# E3.net
KiCad netlist of a schematic drawn in Altium Designer
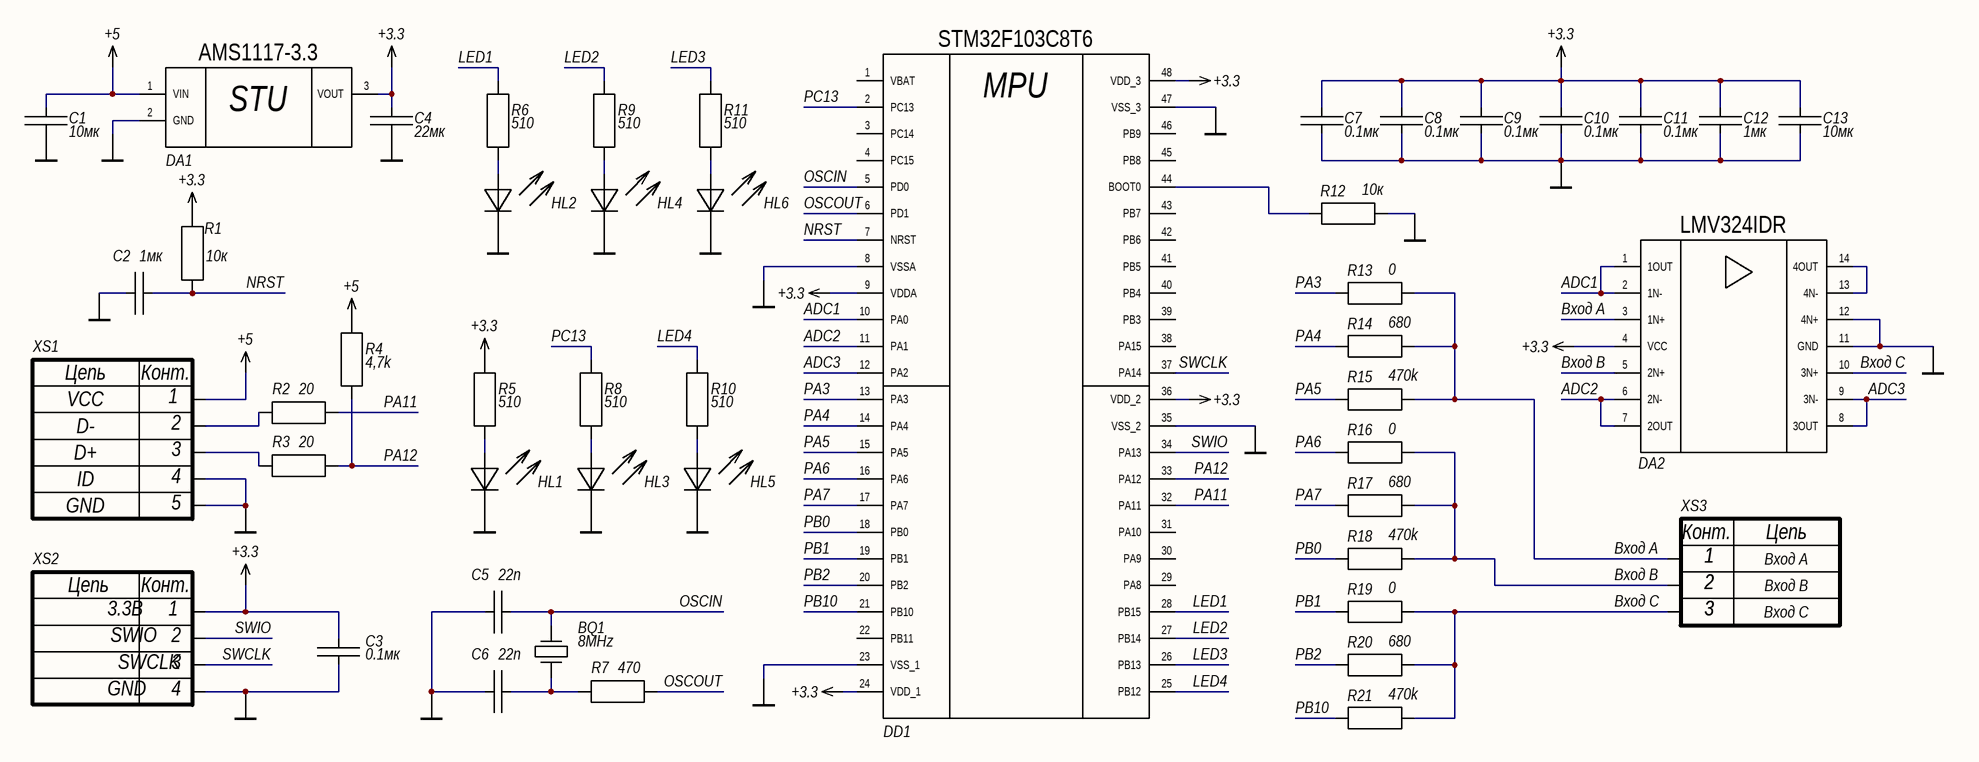
[diagram p0: E3.SchDoc]

(export (version "E")
  (design (tool "Eeschema 10.0.6"))
  (components
    (comp (ref "BQ1")
      (value "8MHz")
      (footprint "PcbLib:Crystal Resonator")
      (libsource (lib "Schlib") (part "Quartz resonator"))
    )
    (comp (ref "C1") (value "10мк") (footprint "PcbLib:C SMD 0603") (libsource (lib "Schlib") (part "C")))
    (comp (ref "C2") (value "1мк") (footprint "PcbLib:C SMD 0603") (libsource (lib "Schlib") (part "C")))
    (comp (ref "C3") (value "0.1мк") (footprint "PcbLib:C SMD 0603") (libsource (lib "Schlib") (part "C")))
    (comp (ref "C4") (value "22мк") (footprint "PcbLib:C SMD 0603") (libsource (lib "Schlib") (part "C")))
    (comp (ref "C5") (value "22п") (footprint "PcbLib:C SMD 0603") (libsource (lib "Schlib") (part "C")))
    (comp (ref "C6") (value "22п") (footprint "PcbLib:C SMD 0603") (libsource (lib "Schlib") (part "C")))
    (comp (ref "C7") (value "0.1мк") (footprint "PcbLib:C SMD 0603") (libsource (lib "Schlib") (part "C")))
    (comp (ref "C8") (value "0.1мк") (footprint "PcbLib:C SMD 0603") (libsource (lib "Schlib") (part "C")))
    (comp (ref "C9") (value "0.1мк") (footprint "PcbLib:C SMD 0603") (libsource (lib "Schlib") (part "C")))
    (comp (ref "C10") (value "0.1мк") (footprint "PcbLib:C SMD 0603") (libsource (lib "Schlib") (part "C")))
    (comp (ref "C11") (value "0.1мк") (footprint "PcbLib:C SMD 0603") (libsource (lib "Schlib") (part "C")))
    (comp (ref "C12") (value "1мк") (footprint "PcbLib:C SMD 0603") (libsource (lib "Schlib") (part "C")))
    (comp (ref "C13") (value "10мк") (footprint "PcbLib:C SMD 0603") (libsource (lib "Schlib") (part "C")))
    (comp (ref "DA1")
      (value "Stabilizer")
      (footprint "SOT230P695X180-4N")
      (libsource (lib "Schlib") (part "Stabilizer"))
    )
    (comp (ref "DA2")
      (value "OpAmp LM358DR [SOIC-14]")
      (footprint "SOP127P600X175-14N")
      (libsource (lib "Schlib") (part "OpAmp LM358DR [SOIC-14]"))
    )
    (comp (ref "DD1")
      (value "STM32F103C8T6 [LQFP-48]")
      (footprint "STM32 [LQFP-48]")
      (description "32bit MCU ARM Cortex-M3 72MHz")
      (libsource (lib "Schlib") (part "STM32F103C8T6 [LQFP-48]"))
    )
    (comp (ref "HL1") (value "LED") (footprint "PcbLib:Led 1206") (libsource (lib "MKlib") (part "LED")))
    (comp (ref "HL2") (value "LED") (footprint "PcbLib:Led 1206") (libsource (lib "MKlib") (part "LED")))
    (comp (ref "HL3") (value "LED") (footprint "PcbLib:Led 1206") (libsource (lib "MKlib") (part "LED")))
    (comp (ref "HL4") (value "LED") (footprint "PcbLib:Led 1206") (libsource (lib "MKlib") (part "LED")))
    (comp (ref "HL5") (value "LED") (footprint "PcbLib:Led 1206") (libsource (lib "MKlib") (part "LED")))
    (comp (ref "HL6") (value "LED") (footprint "PcbLib:Led 1206") (libsource (lib "MKlib") (part "LED")))
    (comp (ref "R1") (value "10к") (footprint "R_SMD_1206") (libsource (lib "Schlib") (part "R")))
    (comp (ref "R2") (value "20") (footprint "R_SMD_1206") (libsource (lib "Schlib") (part "R")))
    (comp (ref "R3") (value "20") (footprint "R_SMD_1206") (libsource (lib "Schlib") (part "R")))
    (comp (ref "R4") (value "4,7k") (footprint "R_SMD_1206") (libsource (lib "Schlib") (part "R")))
    (comp (ref "R5") (value "510") (footprint "R_SMD_1206") (libsource (lib "Schlib") (part "R")))
    (comp (ref "R6") (value "510") (footprint "R_SMD_1206") (libsource (lib "Schlib") (part "R")))
    (comp (ref "R7") (value "470") (footprint "R_SMD_1206") (libsource (lib "Schlib") (part "R")))
    (comp (ref "R8") (value "510") (footprint "R_SMD_1206") (libsource (lib "Schlib") (part "R")))
    (comp (ref "R9") (value "510") (footprint "R_SMD_1206") (libsource (lib "Schlib") (part "R")))
    (comp (ref "R10") (value "510") (footprint "R_SMD_1206") (libsource (lib "Schlib") (part "R")))
    (comp (ref "R11") (value "510") (footprint "R_SMD_1206") (libsource (lib "Schlib") (part "R")))
    (comp (ref "R12") (value "10к") (footprint "R_SMD_1206") (libsource (lib "Schlib") (part "R")))
    (comp (ref "R13") (value "0") (footprint "R_SMD_1206") (libsource (lib "Schlib") (part "R")))
    (comp (ref "R14") (value "680") (footprint "R_SMD_1206") (libsource (lib "Schlib") (part "R")))
    (comp (ref "R15") (value "470k") (footprint "R_SMD_1206") (libsource (lib "Schlib") (part "R")))
    (comp (ref "R16") (value "0") (footprint "R_SMD_1206") (libsource (lib "Schlib") (part "R")))
    (comp (ref "R17") (value "680") (footprint "R_SMD_1206") (libsource (lib "Schlib") (part "R")))
    (comp (ref "R18") (value "470k") (footprint "R_SMD_1206") (libsource (lib "Schlib") (part "R")))
    (comp (ref "R19") (value "0") (footprint "R_SMD_1206") (libsource (lib "Schlib") (part "R")))
    (comp (ref "R20") (value "680") (footprint "R_SMD_1206") (libsource (lib "Schlib") (part "R")))
    (comp (ref "R21") (value "470k") (footprint "R_SMD_1206") (libsource (lib "Schlib") (part "R")))
    (comp (ref "XS1")
      (value "USB_B")
      (footprint "USB 2.0 Type B Mini")
      (libsource (lib "Schlib") (part "USB"))
    )
    (comp (ref "XS2") (value "SWD") (footprint "PLS-4") (libsource (lib "Schlib") (part "XS_SWD")))
    (comp (ref "XS3")
      (value "XS3")
      (footprint "PcbLib:ZIF 14P socket")
      (description "ZIF 14P socket")
      (libsource (lib "Schlib") (part "XS3"))
    )
  )
  (nets
    (net (code "1") (name "+3.3") (class "Default")
      (node (ref "C10") (pin "1") (pinfunction "1_1") (pintype "passive"))
      (node (ref "C11") (pin "1") (pinfunction "1_1") (pintype "passive"))
      (node (ref "C12") (pin "1") (pinfunction "1_1") (pintype "passive"))
      (node (ref "C13") (pin "1") (pinfunction "1_1") (pintype "passive"))
      (node (ref "C3") (pin "1") (pinfunction "1_1") (pintype "passive"))
      (node (ref "C4") (pin "1") (pinfunction "1_1") (pintype "passive"))
      (node (ref "C7") (pin "1") (pinfunction "1_1") (pintype "passive"))
      (node (ref "C8") (pin "1") (pinfunction "1_1") (pintype "passive"))
      (node (ref "C9") (pin "1") (pinfunction "1_1") (pintype "passive"))
      (node (ref "DA1") (pin "3") (pinfunction "VOUT_3") (pintype "passive"))
      (node (ref "DA2") (pin "4") (pinfunction "VCC_4") (pintype "passive"))
      (node (ref "DD1") (pin "24") (pinfunction "VDD_1_24") (pintype "passive"))
      (node (ref "DD1") (pin "36") (pinfunction "VDD_2_36") (pintype "passive"))
      (node (ref "DD1") (pin "48") (pinfunction "VDD_3_48") (pintype "passive"))
      (node (ref "DD1") (pin "9") (pinfunction "VDDA_9") (pintype "passive"))
      (node (ref "R1") (pin "1") (pinfunction "1_1") (pintype "passive"))
      (node (ref "R5") (pin "1") (pinfunction "1_1") (pintype "passive"))
      (node (ref "XS2") (pin "4") (pinfunction "3.3В_4") (pintype "passive"))
    )
    (net (code "2") (name "+5") (class "Default")
      (node (ref "C1") (pin "1") (pinfunction "1_1") (pintype "passive"))
      (node (ref "DA1") (pin "1") (pinfunction "VIN_1") (pintype "passive"))
      (node (ref "R4") (pin "2") (pinfunction "2_2") (pintype "passive"))
      (node (ref "XS1") (pin "1") (pinfunction "1_1") (pintype "passive"))
    )
    (net (code "3") (name "/ADC1") (class "Default")
      (node (ref "DA2") (pin "1") (pinfunction "1OUT_1") (pintype "passive"))
      (node (ref "DA2") (pin "2") (pinfunction "1N-_2") (pintype "passive"))
      (node (ref "DD1") (pin "10") (pinfunction "PA0_10") (pintype "passive"))
    )
    (net (code "4") (name "/ADC2") (class "Default")
      (node (ref "DA2") (pin "6") (pinfunction "2N-_6") (pintype "passive"))
      (node (ref "DA2") (pin "7") (pinfunction "2OUT_7") (pintype "passive"))
      (node (ref "DD1") (pin "11") (pinfunction "PA1_11") (pintype "passive"))
    )
    (net (code "5") (name "/ADC3") (class "Default")
      (node (ref "DA2") (pin "8") (pinfunction "3OUT_8") (pintype "passive"))
      (node (ref "DA2") (pin "9") (pinfunction "3N-_9") (pintype "passive"))
      (node (ref "DD1") (pin "12") (pinfunction "PA2_12") (pintype "passive"))
    )
    (net (code "6") (name "/LED1") (class "Default")
      (node (ref "DD1") (pin "28") (pinfunction "PB15_28") (pintype "passive"))
      (node (ref "R6") (pin "1") (pinfunction "1_1") (pintype "passive"))
    )
    (net (code "7") (name "/LED2") (class "Default")
      (node (ref "DD1") (pin "27") (pinfunction "PB14_27") (pintype "passive"))
      (node (ref "R9") (pin "1") (pinfunction "1_1") (pintype "passive"))
    )
    (net (code "8") (name "/LED3") (class "Default")
      (node (ref "DD1") (pin "26") (pinfunction "PB13_26") (pintype "passive"))
      (node (ref "R11") (pin "1") (pinfunction "1_1") (pintype "passive"))
    )
    (net (code "9") (name "/LED4") (class "Default")
      (node (ref "DD1") (pin "25") (pinfunction "PB12_25") (pintype "passive"))
      (node (ref "R10") (pin "1") (pinfunction "1_1") (pintype "passive"))
    )
    (net (code "10") (name "/NRST") (class "Default")
      (node (ref "C2") (pin "1") (pinfunction "1_1") (pintype "passive"))
      (node (ref "DD1") (pin "7") (pinfunction "NRST_7") (pintype "passive"))
      (node (ref "R1") (pin "2") (pinfunction "2_2") (pintype "passive"))
    )
    (net (code "11") (name "/OSCIN") (class "Default")
      (node (ref "BQ1") (pin "1") (pinfunction "1_1") (pintype "passive"))
      (node (ref "C5") (pin "2") (pinfunction "2_2") (pintype "passive"))
      (node (ref "DD1") (pin "5") (pinfunction "PD0_5") (pintype "passive"))
    )
    (net (code "12") (name "/OSCOUT") (class "Default")
      (node (ref "DD1") (pin "6") (pinfunction "PD1_6") (pintype "passive"))
      (node (ref "R7") (pin "2") (pinfunction "2_2") (pintype "passive"))
    )
    (net (code "13") (name "/PA3") (class "Default")
      (node (ref "DD1") (pin "13") (pinfunction "PA3_13") (pintype "passive"))
      (node (ref "R13") (pin "2") (pinfunction "2_2") (pintype "passive"))
    )
    (net (code "14") (name "/PA4") (class "Default")
      (node (ref "DD1") (pin "14") (pinfunction "PA4_14") (pintype "passive"))
      (node (ref "R14") (pin "2") (pinfunction "2_2") (pintype "passive"))
    )
    (net (code "15") (name "/PA5") (class "Default")
      (node (ref "DD1") (pin "15") (pinfunction "PA5_15") (pintype "passive"))
      (node (ref "R15") (pin "2") (pinfunction "2_2") (pintype "passive"))
    )
    (net (code "16") (name "/PA6") (class "Default")
      (node (ref "DD1") (pin "16") (pinfunction "PA6_16") (pintype "passive"))
      (node (ref "R16") (pin "2") (pinfunction "2_2") (pintype "passive"))
    )
    (net (code "17") (name "/PA7") (class "Default")
      (node (ref "DD1") (pin "17") (pinfunction "PA7_17") (pintype "passive"))
      (node (ref "R17") (pin "2") (pinfunction "2_2") (pintype "passive"))
    )
    (net (code "18") (name "/PA11") (class "Default")
      (node (ref "DD1") (pin "32") (pinfunction "PA11_32") (pintype "passive"))
      (node (ref "R2") (pin "2") (pinfunction "2_2") (pintype "passive"))
    )
    (net (code "19") (name "/PA12") (class "Default")
      (node (ref "DD1") (pin "33") (pinfunction "PA12_33") (pintype "passive"))
      (node (ref "R3") (pin "2") (pinfunction "2_2") (pintype "passive"))
      (node (ref "R4") (pin "1") (pinfunction "1_1") (pintype "passive"))
    )
    (net (code "20") (name "/PB0") (class "Default")
      (node (ref "DD1") (pin "18") (pinfunction "PB0_18") (pintype "passive"))
      (node (ref "R18") (pin "2") (pinfunction "2_2") (pintype "passive"))
    )
    (net (code "21") (name "/PB1") (class "Default")
      (node (ref "DD1") (pin "19") (pinfunction "PB1_19") (pintype "passive"))
      (node (ref "R19") (pin "2") (pinfunction "2_2") (pintype "passive"))
    )
    (net (code "22") (name "/PB2") (class "Default")
      (node (ref "DD1") (pin "20") (pinfunction "PB2_20") (pintype "passive"))
      (node (ref "R20") (pin "2") (pinfunction "2_2") (pintype "passive"))
    )
    (net (code "23") (name "/PB10") (class "Default")
      (node (ref "DD1") (pin "21") (pinfunction "PB10_21") (pintype "passive"))
      (node (ref "R21") (pin "2") (pinfunction "2_2") (pintype "passive"))
    )
    (net (code "24") (name "/PC13") (class "Default")
      (node (ref "DD1") (pin "2") (pinfunction "PC13_2") (pintype "passive"))
      (node (ref "R8") (pin "1") (pinfunction "1_1") (pintype "passive"))
    )
    (net (code "25") (name "/SWCLK") (class "Default")
      (node (ref "DD1") (pin "37") (pinfunction "PA14_37") (pintype "passive"))
      (node (ref "XS2") (pin "2") (pinfunction "SWCLK_2") (pintype "passive"))
    )
    (net (code "26") (name "/SWIO") (class "Default")
      (node (ref "DD1") (pin "34") (pinfunction "PA13_34") (pintype "passive"))
      (node (ref "XS2") (pin "3") (pinfunction "SWIO_3") (pintype "passive"))
    )
    (net (code "27") (name "/Вход A") (class "Default")
      (node (ref "DA2") (pin "3") (pinfunction "1N+_3") (pintype "passive"))
      (node (ref "R13") (pin "1") (pinfunction "1_1") (pintype "passive"))
      (node (ref "R14") (pin "1") (pinfunction "1_1") (pintype "passive"))
      (node (ref "R15") (pin "1") (pinfunction "1_1") (pintype "passive"))
      (node (ref "XS3") (pin "1") (pinfunction "1_1") (pintype "passive"))
    )
    (net (code "28") (name "/Вход B") (class "Default")
      (node (ref "DA2") (pin "5") (pinfunction "2N+_5") (pintype "passive"))
      (node (ref "R16") (pin "1") (pinfunction "1_1") (pintype "passive"))
      (node (ref "R17") (pin "1") (pinfunction "1_1") (pintype "passive"))
      (node (ref "R18") (pin "1") (pinfunction "1_1") (pintype "passive"))
      (node (ref "XS3") (pin "2") (pinfunction "2_2") (pintype "passive"))
    )
    (net (code "29") (name "/Вход C") (class "Default")
      (node (ref "DA2") (pin "10") (pinfunction "3N+_10") (pintype "passive"))
      (node (ref "R19") (pin "1") (pinfunction "1_1") (pintype "passive"))
      (node (ref "R20") (pin "1") (pinfunction "1_1") (pintype "passive"))
      (node (ref "R21") (pin "1") (pinfunction "1_1") (pintype "passive"))
      (node (ref "XS3") (pin "3") (pinfunction "3_3") (pintype "passive"))
    )
    (net (code "30") (name "GND") (class "Default")
      (node (ref "C1") (pin "2") (pinfunction "2_2") (pintype "passive"))
      (node (ref "C10") (pin "2") (pinfunction "2_2") (pintype "passive"))
      (node (ref "C11") (pin "2") (pinfunction "2_2") (pintype "passive"))
      (node (ref "C12") (pin "2") (pinfunction "2_2") (pintype "passive"))
      (node (ref "C13") (pin "2") (pinfunction "2_2") (pintype "passive"))
      (node (ref "C2") (pin "2") (pinfunction "2_2") (pintype "passive"))
      (node (ref "C3") (pin "2") (pinfunction "2_2") (pintype "passive"))
      (node (ref "C4") (pin "2") (pinfunction "2_2") (pintype "passive"))
      (node (ref "C5") (pin "1") (pinfunction "1_1") (pintype "passive"))
      (node (ref "C6") (pin "1") (pinfunction "1_1") (pintype "passive"))
      (node (ref "C7") (pin "2") (pinfunction "2_2") (pintype "passive"))
      (node (ref "C8") (pin "2") (pinfunction "2_2") (pintype "passive"))
      (node (ref "C9") (pin "2") (pinfunction "2_2") (pintype "passive"))
      (node (ref "DA1") (pin "2") (pinfunction "GND_2") (pintype "passive"))
      (node (ref "DA2") (pin "11") (pinfunction "GND_11") (pintype "passive"))
      (node (ref "DA2") (pin "12") (pinfunction "4N+_12") (pintype "passive"))
      (node (ref "DD1") (pin "23") (pinfunction "VSS_1_23") (pintype "passive"))
      (node (ref "DD1") (pin "35") (pinfunction "VSS_2_35") (pintype "passive"))
      (node (ref "DD1") (pin "47") (pinfunction "VSS_3_47") (pintype "passive"))
      (node (ref "DD1") (pin "8") (pinfunction "VSSA_8") (pintype "passive"))
      (node (ref "HL1") (pin "1") (pinfunction "1_1") (pintype "passive"))
      (node (ref "HL2") (pin "1") (pinfunction "1_1") (pintype "passive"))
      (node (ref "HL3") (pin "1") (pinfunction "1_1") (pintype "passive"))
      (node (ref "HL4") (pin "1") (pinfunction "1_1") (pintype "passive"))
      (node (ref "HL5") (pin "1") (pinfunction "1_1") (pintype "passive"))
      (node (ref "HL6") (pin "1") (pinfunction "1_1") (pintype "passive"))
      (node (ref "R12") (pin "1") (pinfunction "1_1") (pintype "passive"))
      (node (ref "XS1") (pin "4") (pinfunction "4_4") (pintype "passive"))
      (node (ref "XS1") (pin "5") (pinfunction "5_5") (pintype "passive"))
      (node (ref "XS2") (pin "1") (pinfunction "GND_1") (pintype "passive"))
    )
    (net (code "31") (name "Net-(BQ1-Pad2)") (class "Default")
      (node (ref "BQ1") (pin "2") (pinfunction "2_2") (pintype "passive"))
      (node (ref "C6") (pin "2") (pinfunction "2_2") (pintype "passive"))
      (node (ref "R7") (pin "1") (pinfunction "1_1") (pintype "passive"))
    )
    (net (code "32") (name "Net-(DA2-4N-)") (class "Default")
      (node (ref "DA2") (pin "13") (pinfunction "4N-_13") (pintype "passive"))
      (node (ref "DA2") (pin "14") (pinfunction "4OUT_14") (pintype "passive"))
    )
    (net (code "33") (name "Net-(DD1-BOOT0)") (class "Default")
      (node (ref "DD1") (pin "44") (pinfunction "BOOT0_44") (pintype "passive"))
      (node (ref "R12") (pin "2") (pinfunction "2_2") (pintype "passive"))
    )
    (net (code "34") (name "Net-(HL1-Pad2)") (class "Default")
      (node (ref "HL1") (pin "2") (pinfunction "2_2") (pintype "passive"))
      (node (ref "R5") (pin "2") (pinfunction "2_2") (pintype "passive"))
    )
    (net (code "35") (name "Net-(HL2-Pad2)") (class "Default")
      (node (ref "HL2") (pin "2") (pinfunction "2_2") (pintype "passive"))
      (node (ref "R6") (pin "2") (pinfunction "2_2") (pintype "passive"))
    )
    (net (code "36") (name "Net-(HL3-Pad2)") (class "Default")
      (node (ref "HL3") (pin "2") (pinfunction "2_2") (pintype "passive"))
      (node (ref "R8") (pin "2") (pinfunction "2_2") (pintype "passive"))
    )
    (net (code "37") (name "Net-(HL4-Pad2)") (class "Default")
      (node (ref "HL4") (pin "2") (pinfunction "2_2") (pintype "passive"))
      (node (ref "R9") (pin "2") (pinfunction "2_2") (pintype "passive"))
    )
    (net (code "38") (name "Net-(HL5-Pad2)") (class "Default")
      (node (ref "HL5") (pin "2") (pinfunction "2_2") (pintype "passive"))
      (node (ref "R10") (pin "2") (pinfunction "2_2") (pintype "passive"))
    )
    (net (code "39") (name "Net-(HL6-Pad2)") (class "Default")
      (node (ref "HL6") (pin "2") (pinfunction "2_2") (pintype "passive"))
      (node (ref "R11") (pin "2") (pinfunction "2_2") (pintype "passive"))
    )
    (net (code "40") (name "Net-(R2-Pad1)") (class "Default")
      (node (ref "R2") (pin "1") (pinfunction "1_1") (pintype "passive"))
      (node (ref "XS1") (pin "2") (pinfunction "2_2") (pintype "passive"))
    )
    (net (code "41") (name "Net-(R3-Pad1)") (class "Default")
      (node (ref "R3") (pin "1") (pinfunction "1_1") (pintype "passive"))
      (node (ref "XS1") (pin "3") (pinfunction "3_3") (pintype "passive"))
    )
    (net (code "42") (name "unconnected-(DD1-PA8-Pad29)") (class "Default")
      (node (ref "DD1") (pin "29") (pinfunction "PA8_29") (pintype "passive"))
    )
    (net (code "43") (name "unconnected-(DD1-PA9-Pad30)") (class "Default")
      (node (ref "DD1") (pin "30") (pinfunction "PA9_30") (pintype "passive"))
    )
    (net (code "44") (name "unconnected-(DD1-PA10-Pad31)") (class "Default")
      (node (ref "DD1") (pin "31") (pinfunction "PA10_31") (pintype "passive"))
    )
    (net (code "45") (name "unconnected-(DD1-PA15-Pad38)") (class "Default")
      (node (ref "DD1") (pin "38") (pinfunction "PA15_38") (pintype "passive"))
    )
    (net (code "46") (name "unconnected-(DD1-PB3-Pad39)") (class "Default")
      (node (ref "DD1") (pin "39") (pinfunction "PB3_39") (pintype "passive"))
    )
    (net (code "47") (name "unconnected-(DD1-PB4-Pad40)") (class "Default")
      (node (ref "DD1") (pin "40") (pinfunction "PB4_40") (pintype "passive"))
    )
    (net (code "48") (name "unconnected-(DD1-PB5-Pad41)") (class "Default")
      (node (ref "DD1") (pin "41") (pinfunction "PB5_41") (pintype "passive"))
    )
    (net (code "49") (name "unconnected-(DD1-PB6-Pad42)") (class "Default")
      (node (ref "DD1") (pin "42") (pinfunction "PB6_42") (pintype "passive"))
    )
    (net (code "50") (name "unconnected-(DD1-PB7-Pad43)") (class "Default")
      (node (ref "DD1") (pin "43") (pinfunction "PB7_43") (pintype "passive"))
    )
    (net (code "51") (name "unconnected-(DD1-PB8-Pad45)") (class "Default")
      (node (ref "DD1") (pin "45") (pinfunction "PB8_45") (pintype "passive"))
    )
    (net (code "52") (name "unconnected-(DD1-PB9-Pad46)") (class "Default")
      (node (ref "DD1") (pin "46") (pinfunction "PB9_46") (pintype "passive"))
    )
    (net (code "53") (name "unconnected-(DD1-PB11-Pad22)") (class "Default")
      (node (ref "DD1") (pin "22") (pinfunction "PB11_22") (pintype "passive"))
    )
    (net (code "54") (name "unconnected-(DD1-PC14-Pad3)") (class "Default")
      (node (ref "DD1") (pin "3") (pinfunction "PC14_3") (pintype "passive"))
    )
    (net (code "55") (name "unconnected-(DD1-PC15-Pad4)") (class "Default")
      (node (ref "DD1") (pin "4") (pinfunction "PC15_4") (pintype "passive"))
    )
    (net (code "56") (name "unconnected-(DD1-VBAT-Pad1)") (class "Default")
      (node (ref "DD1") (pin "1") (pinfunction "VBAT_1") (pintype "passive"))
    )
  )
)
